# Lock_in.net
KiCad netlist of a schematic drawn in EAGLE
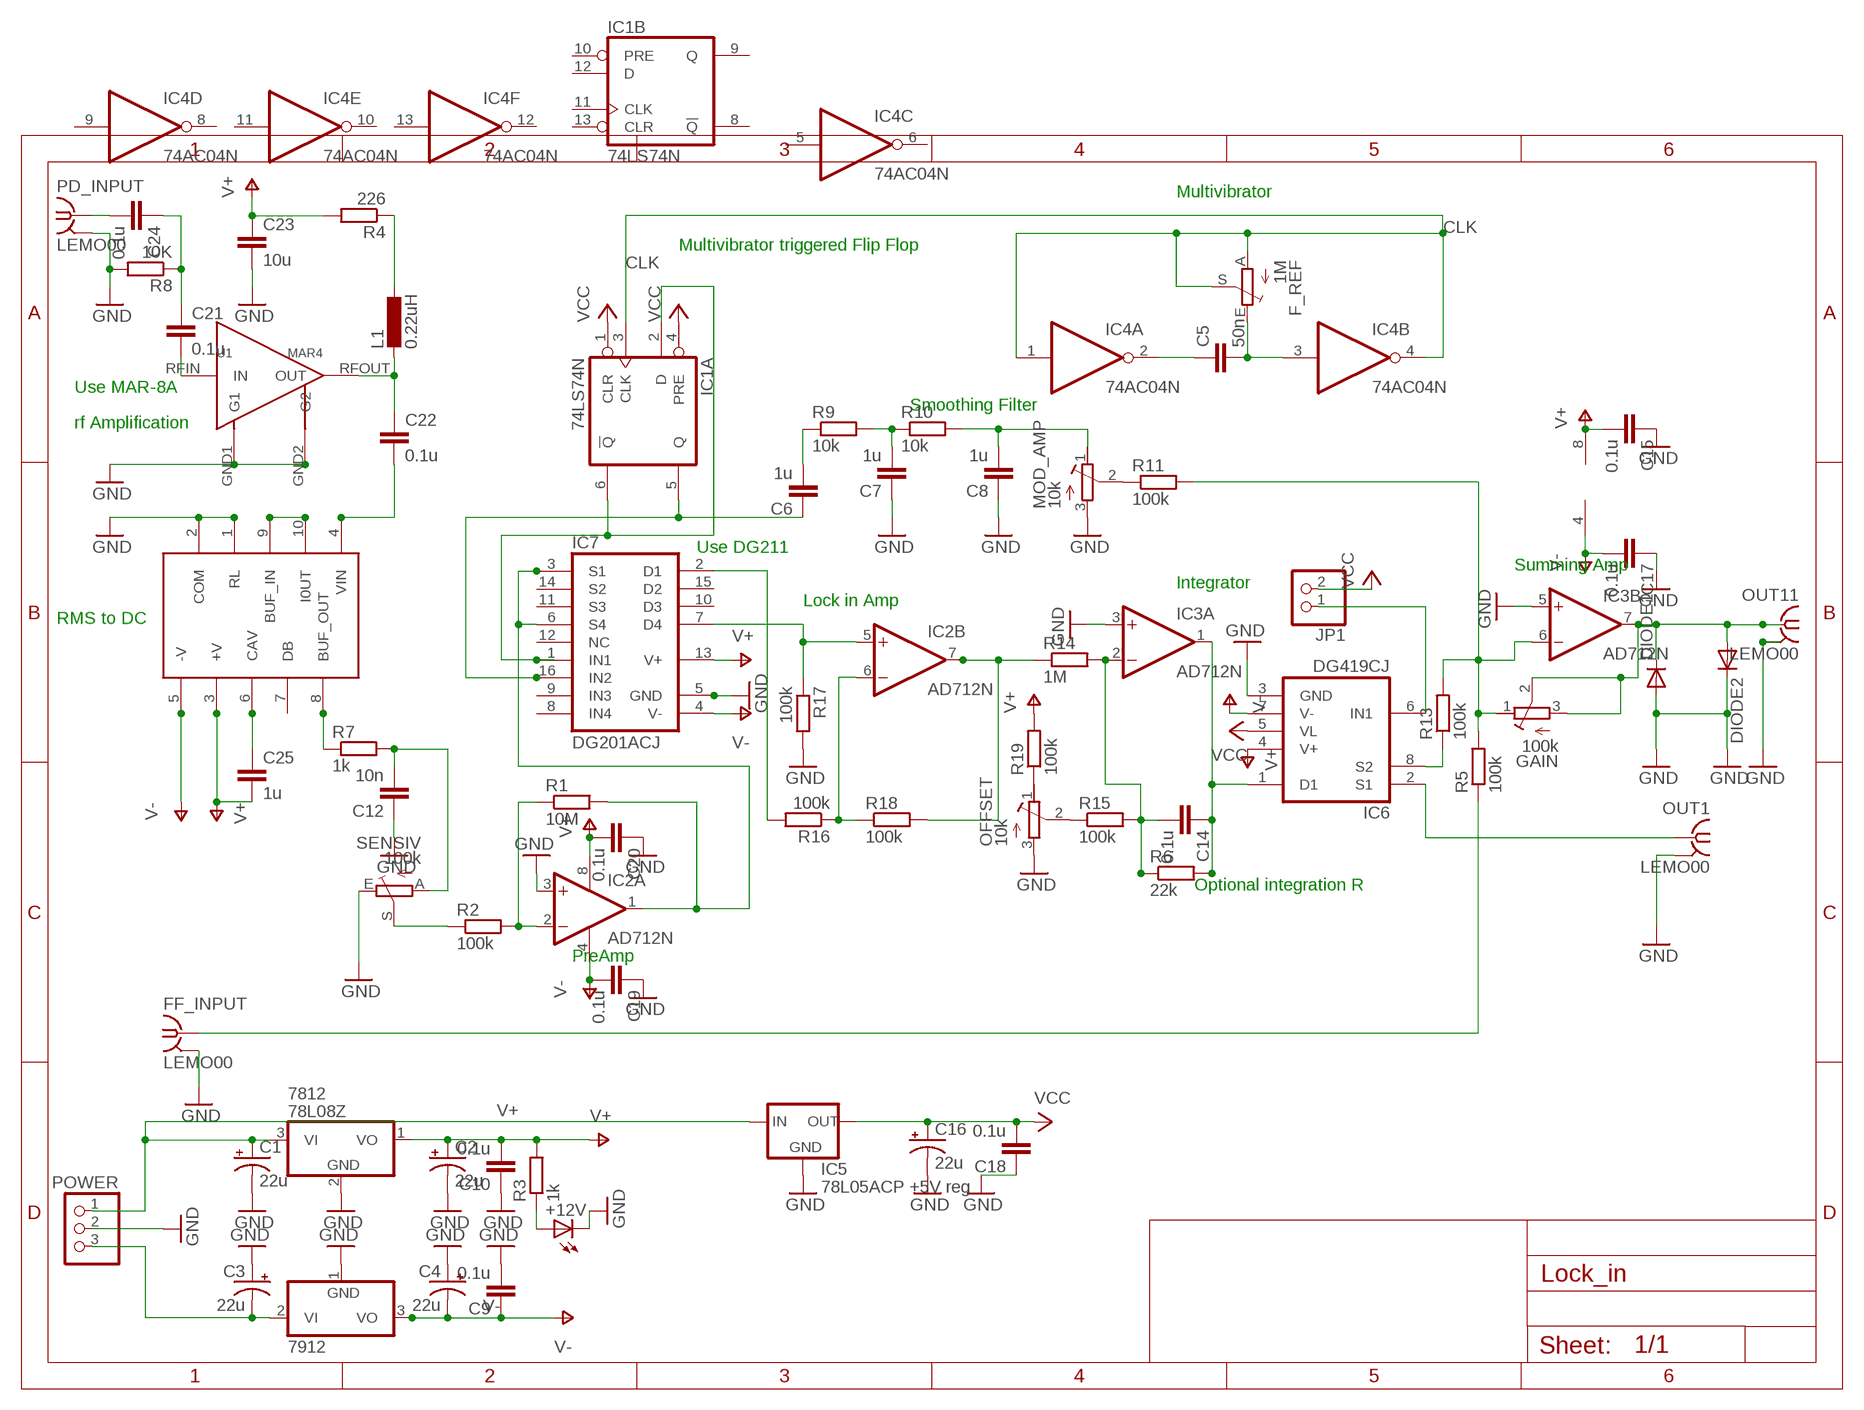
[diagram p0: schematic, sheet 1]

(export (version "E")
  (design (tool "Eeschema 10.0.6"))
  (components
    (comp (ref "+12V")
      (value "LED5MM")
      (footprint "eagle-import:LED5MM")
      (libsource (lib "eagle-import") (part "LED5MM"))
    )
    (comp (ref "7812")
      (value "78L08Z")
      (footprint "eagle-import:TO92")
      (libsource (lib "eagle-import") (part "78ZL08"))
    )
    (comp (ref "7912")
      (value "79L12Z")
      (footprint "eagle-import:TO92")
      (libsource (lib "eagle-import") (part "79ZL12"))
    )
    (comp (ref "C1")
      (value "22u")
      (footprint "eagle-import:E5-4")
      (libsource (lib "eagle-import") (part "CPOL-USE5-4"))
    )
    (comp (ref "C2")
      (value "22u")
      (footprint "eagle-import:E5-4")
      (libsource (lib "eagle-import") (part "CPOL-USE5-4"))
    )
    (comp (ref "C3")
      (value "22u")
      (footprint "eagle-import:E5-4")
      (libsource (lib "eagle-import") (part "CPOL-USE5-4"))
    )
    (comp (ref "C4")
      (value "22u")
      (footprint "eagle-import:E5-4")
      (libsource (lib "eagle-import") (part "CPOL-USE5-4"))
    )
    (comp (ref "C5")
      (value "50n")
      (footprint "eagle-import:C050-024X044")
      (libsource (lib "eagle-import") (part "C-EU050-024X044"))
    )
    (comp (ref "C6")
      (value "1u")
      (footprint "eagle-import:C050-024X044")
      (libsource (lib "eagle-import") (part "C-EU050-024X044"))
    )
    (comp (ref "C7")
      (value "1u")
      (footprint "eagle-import:C050-024X044")
      (libsource (lib "eagle-import") (part "C-EU050-024X044"))
    )
    (comp (ref "C8")
      (value "1u")
      (footprint "eagle-import:C050-024X044")
      (libsource (lib "eagle-import") (part "C-EU050-024X044"))
    )
    (comp (ref "C9")
      (value "0.1u")
      (footprint "eagle-import:C050-024X044")
      (libsource (lib "eagle-import") (part "C-EU050-024X044"))
    )
    (comp (ref "C10")
      (value "0.1u")
      (footprint "eagle-import:C050-024X044")
      (libsource (lib "eagle-import") (part "C-EU050-024X044"))
    )
    (comp (ref "C12")
      (value "10n")
      (footprint "eagle-import:C050-024X044")
      (libsource (lib "eagle-import") (part "C-EU050-024X044"))
    )
    (comp (ref "C14")
      (value "0.1u")
      (footprint "eagle-import:C050-024X044")
      (libsource (lib "eagle-import") (part "C-EU050-024X044"))
    )
    (comp (ref "C15")
      (value "0.1u")
      (footprint "eagle-import:C050-024X044")
      (libsource (lib "eagle-import") (part "C-EU050-024X044"))
    )
    (comp (ref "C16")
      (value "22u")
      (footprint "eagle-import:E5-4")
      (libsource (lib "eagle-import") (part "CPOL-USE5-4"))
    )
    (comp (ref "C17")
      (value "0.1u")
      (footprint "eagle-import:C050-024X044")
      (libsource (lib "eagle-import") (part "C-EU050-024X044"))
    )
    (comp (ref "C18")
      (value "0.1u")
      (footprint "eagle-import:C050-024X044")
      (libsource (lib "eagle-import") (part "C-EU050-024X044"))
    )
    (comp (ref "C19")
      (value "0.1u")
      (footprint "eagle-import:C050-024X044")
      (libsource (lib "eagle-import") (part "C-EU050-024X044"))
    )
    (comp (ref "C20")
      (value "0.1u")
      (footprint "eagle-import:C050-024X044")
      (libsource (lib "eagle-import") (part "C-EU050-024X044"))
    )
    (comp (ref "C21")
      (value "0.1u")
      (footprint "eagle-import:C0805")
      (libsource (lib "eagle-import") (part "C-EUC0805"))
    )
    (comp (ref "C22")
      (value "0.1u")
      (footprint "eagle-import:C0805")
      (libsource (lib "eagle-import") (part "C-EUC0805"))
    )
    (comp (ref "C23")
      (value "10u")
      (footprint "eagle-import:C1206")
      (libsource (lib "eagle-import") (part "C-EUC1206"))
    )
    (comp (ref "C24")
      (value "0.1u")
      (footprint "eagle-import:C0805")
      (libsource (lib "eagle-import") (part "C-EUC0805"))
    )
    (comp (ref "C25")
      (value "1u")
      (footprint "eagle-import:C0805")
      (libsource (lib "eagle-import") (part "C-EUC0805"))
    )
    (comp (ref "DIODE1")
      (value "1N4004")
      (footprint "eagle-import:DO41-10")
      (libsource (lib "eagle-import") (part "1N4004"))
    )
    (comp (ref "DIODE2")
      (value "1N4004")
      (footprint "eagle-import:DO41-10")
      (libsource (lib "eagle-import") (part "1N4004"))
    )
    (comp (ref "FF_INPUT")
      (value "LEMO00")
      (footprint "eagle-import:LEMOPAC.PAC")
      (libsource (lib "eagle-import") (part "LEMO00"))
    )
    (comp (ref "F_REF")
      (value "1M")
      (footprint "eagle-import:S63P")
      (libsource (lib "eagle-import") (part "TRIM_EU-S63P"))
    )
    (comp (ref "GAIN")
      (value "100k")
      (footprint "eagle-import:RTRIM43P")
      (libsource (lib "eagle-import") (part "R-TRIMM43P"))
    )
    (comp (ref "IC1")
      (value "74LS74N")
      (footprint "eagle-import:DIL14")
      (libsource (lib "eagle-import") (part "7474NLS"))
    )
    (comp (ref "IC2")
      (value "AD712N")
      (footprint "eagle-import:DIL08")
      (libsource (lib "eagle-import") (part "AD712N"))
    )
    (comp (ref "IC3")
      (value "AD712N")
      (footprint "eagle-import:DIL08")
      (libsource (lib "eagle-import") (part "AD712N"))
    )
    (comp (ref "IC4")
      (value "74AC04N")
      (footprint "eagle-import:DIL14")
      (libsource (lib "eagle-import") (part "7404NAC"))
    )
    (comp (ref "IC5")
      (value "78L05ACP +5V reg")
      (footprint "eagle-import:78LXX")
      (libsource (lib "eagle-import") (part "78LXX"))
    )
    (comp (ref "IC6")
      (value "DG419CJ")
      (footprint "eagle-import:DIL08")
      (fields (field (name "MF") "MAXIM"))
      (libsource (lib "eagle-import") (part "DG419CJ"))
    )
    (comp (ref "IC7")
      (value "DG201ACJ")
      (footprint "eagle-import:DIL16")
      (libsource (lib "eagle-import") (part "DG201ACJ"))
    )
    (comp (ref "JP1")
      (value "PINHD-1X2")
      (footprint "eagle-import:1X02")
      (libsource (lib "eagle-import") (part "PINHD-1X2"))
    )
    (comp (ref "L1")
      (value "0.22uH")
      (footprint "eagle-import:L3216C")
      (libsource (lib "eagle-import") (part "L-EUL3216C"))
    )
    (comp (ref "MOD_AMP")
      (value "10k")
      (footprint "eagle-import:RTRIM43P")
      (libsource (lib "eagle-import") (part "R-TRIMM43P"))
    )
    (comp (ref "OFFSET")
      (value "10k")
      (footprint "eagle-import:RTRIM43P")
      (libsource (lib "eagle-import") (part "R-TRIMM43P"))
    )
    (comp (ref "OUT1")
      (value "LEMO00")
      (footprint "eagle-import:LEMOPAC.PAC")
      (libsource (lib "eagle-import") (part "LEMO00"))
    )
    (comp (ref "OUT11")
      (value "LEMO00")
      (footprint "eagle-import:LEMOPAC.PAC")
      (libsource (lib "eagle-import") (part "LEMO00"))
    )
    (comp (ref "PD_INPUT")
      (value "LEMO00")
      (footprint "eagle-import:LEMOPAC.PAC")
      (libsource (lib "eagle-import") (part "LEMO00"))
    )
    (comp (ref "POWER")
      (value "PINHD-1X3")
      (footprint "eagle-import:1X03")
      (libsource (lib "eagle-import") (part "PINHD-1X3"))
    )
    (comp (ref "R1")
      (value "10M")
      (footprint "eagle-import:0204_7")
      (libsource (lib "eagle-import") (part "R-EU_0204/7"))
    )
    (comp (ref "R2")
      (value "100k")
      (footprint "eagle-import:0204_7")
      (libsource (lib "eagle-import") (part "R-EU_0204/7"))
    )
    (comp (ref "R3")
      (value "1k")
      (footprint "eagle-import:0204_7")
      (libsource (lib "eagle-import") (part "R-EU_0204/7"))
    )
    (comp (ref "R4")
      (value "226")
      (footprint "eagle-import:R1206")
      (libsource (lib "eagle-import") (part "R-EU_R1206"))
    )
    (comp (ref "R5")
      (value "100k")
      (footprint "eagle-import:0204_7")
      (libsource (lib "eagle-import") (part "R-EU_0204/7"))
    )
    (comp (ref "R6")
      (value "22k")
      (footprint "eagle-import:0204_7")
      (libsource (lib "eagle-import") (part "R-EU_0204/7"))
    )
    (comp (ref "R7")
      (value "1k")
      (footprint "eagle-import:0204_7")
      (libsource (lib "eagle-import") (part "R-EU_0204/7"))
    )
    (comp (ref "R8")
      (value "10K")
      (footprint "eagle-import:R1206")
      (libsource (lib "eagle-import") (part "R-EU_R1206"))
    )
    (comp (ref "R9")
      (value "10k")
      (footprint "eagle-import:0204_7")
      (libsource (lib "eagle-import") (part "R-EU_0204/7"))
    )
    (comp (ref "R10")
      (value "10k")
      (footprint "eagle-import:0204_7")
      (libsource (lib "eagle-import") (part "R-EU_0204/7"))
    )
    (comp (ref "R11")
      (value "100k")
      (footprint "eagle-import:0204_7")
      (libsource (lib "eagle-import") (part "R-EU_0204/7"))
    )
    (comp (ref "R13")
      (value "100k")
      (footprint "eagle-import:0204_7")
      (libsource (lib "eagle-import") (part "R-EU_0204/7"))
    )
    (comp (ref "R14")
      (value "1M")
      (footprint "eagle-import:0204_7")
      (libsource (lib "eagle-import") (part "R-EU_0204/7"))
    )
    (comp (ref "R15")
      (value "100k")
      (footprint "eagle-import:0204_7")
      (libsource (lib "eagle-import") (part "R-EU_0204/7"))
    )
    (comp (ref "R16")
      (value "100k")
      (footprint "eagle-import:0204_7")
      (libsource (lib "eagle-import") (part "R-EU_0204/7"))
    )
    (comp (ref "R17")
      (value "100k")
      (footprint "eagle-import:0204_7")
      (libsource (lib "eagle-import") (part "R-EU_0204/7"))
    )
    (comp (ref "R18")
      (value "100k")
      (footprint "eagle-import:0204_7")
      (libsource (lib "eagle-import") (part "R-EU_0204/7"))
    )
    (comp (ref "R19")
      (value "100k")
      (footprint "eagle-import:0204_7")
      (libsource (lib "eagle-import") (part "R-EU_0204/7"))
    )
    (comp (ref "SENSIV")
      (value "100k")
      (footprint "eagle-import:S63P")
      (libsource (lib "eagle-import") (part "TRIM_EU-S63P"))
    )
    (comp (ref "U$1")
      (value "AD636")
      (footprint "eagle-import:TO100")
      (libsource (lib "eagle-import") (part "AD636"))
    )
    (comp (ref "U1")
      (value "MAR4")
      (footprint "eagle-import:VV105")
      (libsource (lib "eagle-import") (part "MAR4"))
    )
  )
  (nets
    (net (code "1") (name "/CLK") (class "Default")
      (node (ref "F_REF") (pin "A") (pinfunction "A_A") (pintype "passive"))
      (node (ref "F_REF") (pin "S") (pinfunction "S_S") (pintype "passive"))
      (node (ref "IC1") (pin "3") (pinfunction "CLK_3") (pintype "input"))
      (node (ref "IC4") (pin "1") (pinfunction "I_1") (pintype "input"))
      (node (ref "IC4") (pin "4") (pinfunction "O_4") (pintype "output"))
    )
    (net (code "2") (name "GND") (class "Default")
      (node (ref "+12V") (pin "K") (pinfunction "C_K") (pintype "passive"))
      (node (ref "7812") (pin "2") (pinfunction "GND_2") (pintype "passive"))
      (node (ref "7912") (pin "1") (pinfunction "GND_1") (pintype "passive"))
      (node (ref "C1") (pin "-") (pinfunction "-_-") (pintype "passive"))
      (node (ref "C10") (pin "1") (pinfunction "1_1") (pintype "passive"))
      (node (ref "C12") (pin "1") (pinfunction "1_1") (pintype "passive"))
      (node (ref "C15") (pin "1") (pinfunction "1_1") (pintype "passive"))
      (node (ref "C16") (pin "-") (pinfunction "-_-") (pintype "passive"))
      (node (ref "C17") (pin "1") (pinfunction "1_1") (pintype "passive"))
      (node (ref "C18") (pin "1") (pinfunction "1_1") (pintype "passive"))
      (node (ref "C19") (pin "1") (pinfunction "1_1") (pintype "passive"))
      (node (ref "C2") (pin "-") (pinfunction "-_-") (pintype "passive"))
      (node (ref "C20") (pin "1") (pinfunction "1_1") (pintype "passive"))
      (node (ref "C23") (pin "2") (pinfunction "2_2") (pintype "passive"))
      (node (ref "C3") (pin "+") (pinfunction "+_+") (pintype "passive"))
      (node (ref "C4") (pin "+") (pinfunction "+_+") (pintype "passive"))
      (node (ref "C7") (pin "1") (pinfunction "1_1") (pintype "passive"))
      (node (ref "C8") (pin "1") (pinfunction "1_1") (pintype "passive"))
      (node (ref "C9") (pin "2") (pinfunction "2_2") (pintype "passive"))
      (node (ref "DIODE1") (pin "A") (pinfunction "A_A") (pintype "passive"))
      (node (ref "DIODE2") (pin "C") (pinfunction "C_C") (pintype "passive"))
      (node (ref "FF_INPUT") (pin "2") (pinfunction "GND_2") (pintype "power_in"))
      (node (ref "FF_INPUT") (pin "3") (pinfunction "GND_3") (pintype "power_in"))
      (node (ref "FF_INPUT") (pin "4") (pinfunction "GND_4") (pintype "power_in"))
      (node (ref "FF_INPUT") (pin "5") (pinfunction "GND_5") (pintype "power_in"))
      (node (ref "IC2") (pin "3") (pinfunction "+IN_3") (pintype "input"))
      (node (ref "IC3") (pin "3") (pinfunction "+IN_3") (pintype "input"))
      (node (ref "IC3") (pin "5") (pinfunction "+IN_5") (pintype "input"))
      (node (ref "IC5") (pin "GND") (pinfunction "GND_GND") (pintype "input"))
      (node (ref "IC6") (pin "3") (pinfunction "GND_3") (pintype "power_in"))
      (node (ref "IC7") (pin "5") (pinfunction "GND_5") (pintype "power_in"))
      (node (ref "MOD_AMP") (pin "3") (pinfunction "E_3") (pintype "passive"))
      (node (ref "OFFSET") (pin "3") (pinfunction "E_3") (pintype "passive"))
      (node (ref "OUT1") (pin "2") (pinfunction "GND_2") (pintype "power_in"))
      (node (ref "OUT1") (pin "3") (pinfunction "GND_3") (pintype "power_in"))
      (node (ref "OUT1") (pin "4") (pinfunction "GND_4") (pintype "power_in"))
      (node (ref "OUT1") (pin "5") (pinfunction "GND_5") (pintype "power_in"))
      (node (ref "OUT11") (pin "2") (pinfunction "GND_2") (pintype "power_in"))
      (node (ref "OUT11") (pin "3") (pinfunction "GND_3") (pintype "power_in"))
      (node (ref "OUT11") (pin "4") (pinfunction "GND_4") (pintype "power_in"))
      (node (ref "OUT11") (pin "5") (pinfunction "GND_5") (pintype "power_in"))
      (node (ref "PD_INPUT") (pin "2") (pinfunction "GND_2") (pintype "power_in"))
      (node (ref "PD_INPUT") (pin "3") (pinfunction "GND_3") (pintype "power_in"))
      (node (ref "PD_INPUT") (pin "4") (pinfunction "GND_4") (pintype "power_in"))
      (node (ref "PD_INPUT") (pin "5") (pinfunction "GND_5") (pintype "power_in"))
      (node (ref "POWER") (pin "2") (pinfunction "2_2") (pintype "passive"))
      (node (ref "R17") (pin "2") (pinfunction "2_2") (pintype "passive"))
      (node (ref "R8") (pin "2") (pinfunction "2_2") (pintype "passive"))
      (node (ref "SENSIV") (pin "E") (pinfunction "E_E") (pintype "passive"))
      (node (ref "U$1") (pin "1") (pinfunction "RL_1") (pintype "output"))
      (node (ref "U$1") (pin "2") (pinfunction "COM_2") (pintype "power_in"))
      (node (ref "U1") (pin "GND1") (pinfunction "G1_GND1") (pintype "power_in"))
      (node (ref "U1") (pin "GND2") (pinfunction "G2_GND2") (pintype "power_in"))
    )
    (net (code "3") (name "Net-(+12V-PadA)") (class "Default")
      (node (ref "+12V") (pin "A") (pinfunction "A_A") (pintype "passive"))
      (node (ref "R3") (pin "1") (pinfunction "1_1") (pintype "passive"))
    )
    (net (code "4") (name "Net-(7812-VI)") (class "Default")
      (node (ref "7812") (pin "3") (pinfunction "VI_3") (pintype "input"))
      (node (ref "C1") (pin "+") (pinfunction "+_+") (pintype "passive"))
      (node (ref "IC5") (pin "IN") (pinfunction "IN_IN") (pintype "input"))
      (node (ref "POWER") (pin "1") (pinfunction "1_1") (pintype "passive"))
    )
    (net (code "5") (name "Net-(7912-VI)") (class "Default")
      (node (ref "7912") (pin "2") (pinfunction "VI_2") (pintype "input"))
      (node (ref "C3") (pin "-") (pinfunction "-_-") (pintype "passive"))
      (node (ref "POWER") (pin "3") (pinfunction "3_3") (pintype "passive"))
    )
    (net (code "6") (name "Net-(C6-Pad2)") (class "Default")
      (node (ref "C6") (pin "2") (pinfunction "2_2") (pintype "passive"))
      (node (ref "R9") (pin "1") (pinfunction "1_1") (pintype "passive"))
    )
    (net (code "7") (name "Net-(C7-Pad2)") (class "Default")
      (node (ref "C7") (pin "2") (pinfunction "2_2") (pintype "passive"))
      (node (ref "R10") (pin "1") (pinfunction "1_1") (pintype "passive"))
      (node (ref "R9") (pin "2") (pinfunction "2_2") (pintype "passive"))
    )
    (net (code "8") (name "Net-(C12-Pad2)") (class "Default")
      (node (ref "C12") (pin "2") (pinfunction "2_2") (pintype "passive"))
      (node (ref "R7") (pin "2") (pinfunction "2_2") (pintype "passive"))
      (node (ref "SENSIV") (pin "A") (pinfunction "A_A") (pintype "passive"))
    )
    (net (code "9") (name "Net-(C21-Pad1)") (class "Default")
      (node (ref "C21") (pin "1") (pinfunction "1_1") (pintype "passive"))
      (node (ref "C24") (pin "1") (pinfunction "1_1") (pintype "passive"))
      (node (ref "R8") (pin "1") (pinfunction "1_1") (pintype "passive"))
    )
    (net (code "10") (name "Net-(C24-Pad2)") (class "Default")
      (node (ref "C24") (pin "2") (pinfunction "2_2") (pintype "passive"))
      (node (ref "PD_INPUT") (pin "1") (pinfunction "1_1") (pintype "passive"))
    )
    (net (code "11") (name "Net-(FF_INPUT-Pad1)") (class "Default")
      (node (ref "FF_INPUT") (pin "1") (pinfunction "1_1") (pintype "passive"))
      (node (ref "R5") (pin "1") (pinfunction "1_1") (pintype "passive"))
    )
    (net (code "12") (name "Net-(GAIN-A)") (class "Default")
      (node (ref "GAIN") (pin "1") (pinfunction "A_1") (pintype "passive"))
      (node (ref "IC3") (pin "6") (pinfunction "-IN_6") (pintype "input"))
      (node (ref "R11") (pin "2") (pinfunction "2_2") (pintype "passive"))
      (node (ref "R13") (pin "2") (pinfunction "2_2") (pintype "passive"))
      (node (ref "R5") (pin "2") (pinfunction "2_2") (pintype "passive"))
    )
    (net (code "13") (name "Net-(GAIN-E)") (class "Default")
      (node (ref "DIODE1") (pin "C") (pinfunction "C_C") (pintype "passive"))
      (node (ref "DIODE2") (pin "A") (pinfunction "A_A") (pintype "passive"))
      (node (ref "GAIN") (pin "2") (pinfunction "S_2") (pintype "passive"))
      (node (ref "GAIN") (pin "3") (pinfunction "E_3") (pintype "passive"))
      (node (ref "IC3") (pin "7") (pinfunction "OUT_7") (pintype "output"))
      (node (ref "OUT11") (pin "1") (pinfunction "1_1") (pintype "passive"))
    )
    (net (code "14") (name "Net-(IC1A-D)") (class "Default")
      (node (ref "IC1") (pin "2") (pinfunction "D_2") (pintype "input"))
      (node (ref "IC1") (pin "6") (pinfunction "~{Q}_6") (pintype "output"))
      (node (ref "IC7") (pin "1") (pinfunction "IN1_1") (pintype "input"))
    )
    (net (code "15") (name "Net-(IC1A-Q)") (class "Default")
      (node (ref "C6") (pin "1") (pinfunction "1_1") (pintype "passive"))
      (node (ref "IC1") (pin "5") (pinfunction "Q_5") (pintype "output"))
      (node (ref "IC7") (pin "16") (pinfunction "IN2_16") (pintype "input"))
    )
    (net (code "16") (name "Net-(IC2A--IN)") (class "Default")
      (node (ref "IC2") (pin "2") (pinfunction "-IN_2") (pintype "input"))
      (node (ref "R1") (pin "1") (pinfunction "1_1") (pintype "passive"))
      (node (ref "R2") (pin "2") (pinfunction "2_2") (pintype "passive"))
    )
    (net (code "17") (name "Net-(IC2A-OUT)") (class "Default")
      (node (ref "IC2") (pin "1") (pinfunction "OUT_1") (pintype "output"))
      (node (ref "IC7") (pin "3") (pinfunction "S1_3") (pintype "passive"))
      (node (ref "IC7") (pin "6") (pinfunction "S4_6") (pintype "passive"))
      (node (ref "R1") (pin "2") (pinfunction "2_2") (pintype "passive"))
    )
    (net (code "18") (name "Net-(IC2B-+IN)") (class "Default")
      (node (ref "IC2") (pin "5") (pinfunction "+IN_5") (pintype "input"))
      (node (ref "IC7") (pin "7") (pinfunction "D4_7") (pintype "passive"))
      (node (ref "R17") (pin "1") (pinfunction "1_1") (pintype "passive"))
    )
    (net (code "19") (name "Net-(IC2B--IN)") (class "Default")
      (node (ref "IC2") (pin "6") (pinfunction "-IN_6") (pintype "input"))
      (node (ref "R16") (pin "1") (pinfunction "1_1") (pintype "passive"))
      (node (ref "R18") (pin "1") (pinfunction "1_1") (pintype "passive"))
    )
    (net (code "20") (name "Net-(IC2B-OUT)") (class "Default")
      (node (ref "IC2") (pin "7") (pinfunction "OUT_7") (pintype "output"))
      (node (ref "R14") (pin "1") (pinfunction "1_1") (pintype "passive"))
      (node (ref "R18") (pin "2") (pinfunction "2_2") (pintype "passive"))
    )
    (net (code "21") (name "Net-(IC3A--IN)") (class "Default")
      (node (ref "C14") (pin "2") (pinfunction "2_2") (pintype "passive"))
      (node (ref "IC3") (pin "2") (pinfunction "-IN_2") (pintype "input"))
      (node (ref "R14") (pin "2") (pinfunction "2_2") (pintype "passive"))
      (node (ref "R15") (pin "2") (pinfunction "2_2") (pintype "passive"))
      (node (ref "R6") (pin "1") (pinfunction "1_1") (pintype "passive"))
    )
    (net (code "22") (name "Net-(IC3A-OUT)") (class "Default")
      (node (ref "C14") (pin "1") (pinfunction "1_1") (pintype "passive"))
      (node (ref "IC3") (pin "1") (pinfunction "OUT_1") (pintype "output"))
      (node (ref "IC6") (pin "1") (pinfunction "D1_1") (pintype "passive"))
      (node (ref "R6") (pin "2") (pinfunction "2_2") (pintype "passive"))
    )
    (net (code "23") (name "Net-(IC4A-O)") (class "Default")
      (node (ref "C5") (pin "1") (pinfunction "1_1") (pintype "passive"))
      (node (ref "IC4") (pin "2") (pinfunction "O_2") (pintype "output"))
    )
    (net (code "24") (name "Net-(IC4B-I)") (class "Default")
      (node (ref "C5") (pin "2") (pinfunction "2_2") (pintype "passive"))
      (node (ref "F_REF") (pin "E") (pinfunction "E_E") (pintype "passive"))
      (node (ref "IC4") (pin "3") (pinfunction "I_3") (pintype "input"))
    )
    (net (code "25") (name "Net-(IC6-IN1)") (class "Default")
      (node (ref "IC6") (pin "6") (pinfunction "IN1_6") (pintype "input"))
      (node (ref "JP1") (pin "1") (pinfunction "1_1") (pintype "passive"))
    )
    (net (code "26") (name "Net-(IC6-S1)") (class "Default")
      (node (ref "IC6") (pin "2") (pinfunction "S1_2") (pintype "passive"))
      (node (ref "OUT1") (pin "1") (pinfunction "1_1") (pintype "passive"))
    )
    (net (code "27") (name "Net-(IC6-S2)") (class "Default")
      (node (ref "IC6") (pin "8") (pinfunction "S2_8") (pintype "passive"))
      (node (ref "R13") (pin "1") (pinfunction "1_1") (pintype "passive"))
    )
    (net (code "28") (name "Net-(IC7-D1)") (class "Default")
      (node (ref "IC7") (pin "2") (pinfunction "D1_2") (pintype "passive"))
      (node (ref "R16") (pin "2") (pinfunction "2_2") (pintype "passive"))
    )
    (net (code "29") (name "Net-(L1-Pad1)") (class "Default")
      (node (ref "L1") (pin "1") (pinfunction "1_1") (pintype "passive"))
      (node (ref "R4") (pin "1") (pinfunction "1_1") (pintype "passive"))
    )
    (net (code "30") (name "Net-(MOD_AMP-A)") (class "Default")
      (node (ref "C8") (pin "2") (pinfunction "2_2") (pintype "passive"))
      (node (ref "MOD_AMP") (pin "1") (pinfunction "A_1") (pintype "passive"))
      (node (ref "R10") (pin "2") (pinfunction "2_2") (pintype "passive"))
    )
    (net (code "31") (name "Net-(MOD_AMP-S)") (class "Default")
      (node (ref "MOD_AMP") (pin "2") (pinfunction "S_2") (pintype "passive"))
      (node (ref "R11") (pin "1") (pinfunction "1_1") (pintype "passive"))
    )
    (net (code "32") (name "Net-(OFFSET-A)") (class "Default")
      (node (ref "OFFSET") (pin "1") (pinfunction "A_1") (pintype "passive"))
      (node (ref "R19") (pin "1") (pinfunction "1_1") (pintype "passive"))
    )
    (net (code "33") (name "Net-(OFFSET-S)") (class "Default")
      (node (ref "OFFSET") (pin "2") (pinfunction "S_2") (pintype "passive"))
      (node (ref "R15") (pin "1") (pinfunction "1_1") (pintype "passive"))
    )
    (net (code "34") (name "Net-(R2-Pad1)") (class "Default")
      (node (ref "R2") (pin "1") (pinfunction "1_1") (pintype "passive"))
      (node (ref "SENSIV") (pin "S") (pinfunction "S_S") (pintype "passive"))
    )
    (net (code "35") (name "Net-(U$1-BUF_IN)") (class "Default")
      (node (ref "U$1") (pin "10") (pinfunction "I0UT_10") (pintype "output"))
      (node (ref "U$1") (pin "9") (pinfunction "BUF_IN_9") (pintype "bidirectional"))
    )
    (net (code "36") (name "Net-(U$1-BUF_OUT)") (class "Default")
      (node (ref "R7") (pin "1") (pinfunction "1_1") (pintype "passive"))
      (node (ref "U$1") (pin "8") (pinfunction "BUF_OUT_8") (pintype "output"))
    )
    (net (code "37") (name "Net-(U$1-CAV)") (class "Default")
      (node (ref "C25") (pin "1") (pinfunction "1_1") (pintype "passive"))
      (node (ref "U$1") (pin "6") (pinfunction "CAV_6") (pintype "input"))
    )
    (net (code "38") (name "Net-(U$1-VIN)") (class "Default")
      (node (ref "C22") (pin "2") (pinfunction "2_2") (pintype "passive"))
      (node (ref "U$1") (pin "4") (pinfunction "VIN_4") (pintype "input"))
    )
    (net (code "39") (name "Net-(U1-IN)") (class "Default")
      (node (ref "C21") (pin "2") (pinfunction "2_2") (pintype "passive"))
      (node (ref "U1") (pin "RFIN") (pinfunction "IN_RFIN") (pintype "input"))
    )
    (net (code "40") (name "Net-(U1-OUT)") (class "Default")
      (node (ref "C22") (pin "1") (pinfunction "1_1") (pintype "passive"))
      (node (ref "L1") (pin "2") (pinfunction "2_2") (pintype "passive"))
      (node (ref "U1") (pin "RFOUT") (pinfunction "OUT_RFOUT") (pintype "output"))
    )
    (net (code "41") (name "V+") (class "Default")
      (node (ref "7812") (pin "1") (pinfunction "VO_1") (pintype "passive"))
      (node (ref "C10") (pin "2") (pinfunction "2_2") (pintype "passive"))
      (node (ref "C15") (pin "2") (pinfunction "2_2") (pintype "passive"))
      (node (ref "C2") (pin "+") (pinfunction "+_+") (pintype "passive"))
      (node (ref "C20") (pin "2") (pinfunction "2_2") (pintype "passive"))
      (node (ref "C23") (pin "1") (pinfunction "1_1") (pintype "passive"))
      (node (ref "C25") (pin "2") (pinfunction "2_2") (pintype "passive"))
      (node (ref "IC2") (pin "8") (pinfunction "V+_8") (pintype "power_in"))
      (node (ref "IC3") (pin "8") (pinfunction "V+_8") (pintype "power_in"))
      (node (ref "IC6") (pin "4") (pinfunction "V+_4") (pintype "power_in"))
      (node (ref "IC7") (pin "13") (pinfunction "V+_13") (pintype "power_in"))
      (node (ref "R19") (pin "2") (pinfunction "2_2") (pintype "passive"))
      (node (ref "R3") (pin "2") (pinfunction "2_2") (pintype "passive"))
      (node (ref "R4") (pin "2") (pinfunction "2_2") (pintype "passive"))
      (node (ref "U$1") (pin "3") (pinfunction "+V_3") (pintype "power_in"))
    )
    (net (code "42") (name "V-") (class "Default")
      (node (ref "7912") (pin "3") (pinfunction "VO_3") (pintype "passive"))
      (node (ref "C17") (pin "2") (pinfunction "2_2") (pintype "passive"))
      (node (ref "C19") (pin "2") (pinfunction "2_2") (pintype "passive"))
      (node (ref "C4") (pin "-") (pinfunction "-_-") (pintype "passive"))
      (node (ref "C9") (pin "1") (pinfunction "1_1") (pintype "passive"))
      (node (ref "IC2") (pin "4") (pinfunction "V-_4") (pintype "power_in"))
      (node (ref "IC3") (pin "4") (pinfunction "V-_4") (pintype "power_in"))
      (node (ref "IC6") (pin "7") (pinfunction "V-_7") (pintype "power_in"))
      (node (ref "IC7") (pin "4") (pinfunction "V-_4") (pintype "power_in"))
      (node (ref "U$1") (pin "5") (pinfunction "-V_5") (pintype "power_in"))
    )
    (net (code "43") (name "VCC") (class "Default")
      (node (ref "C16") (pin "+") (pinfunction "+_+") (pintype "passive"))
      (node (ref "C18") (pin "2") (pinfunction "2_2") (pintype "passive"))
      (node (ref "IC1") (pin "1") (pinfunction "CLR_1") (pintype "input"))
      (node (ref "IC1") (pin "4") (pinfunction "PRE_4") (pintype "input"))
      (node (ref "IC5") (pin "OUT") (pinfunction "OUT_OUT") (pintype "passive"))
      (node (ref "IC6") (pin "5") (pinfunction "VL_5") (pintype "power_in"))
      (node (ref "JP1") (pin "2") (pinfunction "2_2") (pintype "passive"))
    )
    (net (code "44") (name "unconnected-(IC1B-CLK-Pad11)") (class "Default")
      (node (ref "IC1") (pin "11") (pinfunction "CLK_11") (pintype "input"))
    )
    (net (code "45") (name "unconnected-(IC1B-CLR-Pad13)") (class "Default")
      (node (ref "IC1") (pin "13") (pinfunction "CLR_13") (pintype "input"))
    )
    (net (code "46") (name "unconnected-(IC1B-D-Pad12)") (class "Default")
      (node (ref "IC1") (pin "12") (pinfunction "D_12") (pintype "input"))
    )
    (net (code "47") (name "unconnected-(IC1B-PRE-Pad10)") (class "Default")
      (node (ref "IC1") (pin "10") (pinfunction "PRE_10") (pintype "input"))
    )
    (net (code "48") (name "unconnected-(IC1B-Q-Pad9)") (class "Default")
      (node (ref "IC1") (pin "9") (pinfunction "Q_9") (pintype "output"))
    )
    (net (code "49") (name "unconnected-(IC1B-~{Q}-Pad8)") (class "Default")
      (node (ref "IC1") (pin "8") (pinfunction "~{Q}_8") (pintype "output"))
    )
    (net (code "50") (name "unconnected-(IC4C-I-Pad5)") (class "Default")
      (node (ref "IC4") (pin "5") (pinfunction "I_5") (pintype "input"))
    )
    (net (code "51") (name "unconnected-(IC4C-O-Pad6)") (class "Default")
      (node (ref "IC4") (pin "6") (pinfunction "O_6") (pintype "output"))
    )
    (net (code "52") (name "unconnected-(IC4D-I-Pad9)") (class "Default")
      (node (ref "IC4") (pin "9") (pinfunction "I_9") (pintype "input"))
    )
    (net (code "53") (name "unconnected-(IC4D-O-Pad8)") (class "Default")
      (node (ref "IC4") (pin "8") (pinfunction "O_8") (pintype "output"))
    )
    (net (code "54") (name "unconnected-(IC4E-I-Pad11)") (class "Default")
      (node (ref "IC4") (pin "11") (pinfunction "I_11") (pintype "input"))
    )
    (net (code "55") (name "unconnected-(IC4E-O-Pad10)") (class "Default")
      (node (ref "IC4") (pin "10") (pinfunction "O_10") (pintype "output"))
    )
    (net (code "56") (name "unconnected-(IC4F-I-Pad13)") (class "Default")
      (node (ref "IC4") (pin "13") (pinfunction "I_13") (pintype "input"))
    )
    (net (code "57") (name "unconnected-(IC4F-O-Pad12)") (class "Default")
      (node (ref "IC4") (pin "12") (pinfunction "O_12") (pintype "output"))
    )
    (net (code "58") (name "unconnected-(IC7-D2-Pad15)") (class "Default")
      (node (ref "IC7") (pin "15") (pinfunction "D2_15") (pintype "passive"))
    )
    (net (code "59") (name "unconnected-(IC7-D3-Pad10)") (class "Default")
      (node (ref "IC7") (pin "10") (pinfunction "D3_10") (pintype "passive"))
    )
    (net (code "60") (name "unconnected-(IC7-IN3-Pad9)") (class "Default")
      (node (ref "IC7") (pin "9") (pinfunction "IN3_9") (pintype "input"))
    )
    (net (code "61") (name "unconnected-(IC7-IN4-Pad8)") (class "Default")
      (node (ref "IC7") (pin "8") (pinfunction "IN4_8") (pintype "input"))
    )
    (net (code "62") (name "unconnected-(IC7-NC-Pad12)") (class "Default")
      (node (ref "IC7") (pin "12") (pinfunction "NC_12") (pintype "no_connect"))
    )
    (net (code "63") (name "unconnected-(IC7-S2-Pad14)") (class "Default")
      (node (ref "IC7") (pin "14") (pinfunction "S2_14") (pintype "passive"))
    )
    (net (code "64") (name "unconnected-(IC7-S3-Pad11)") (class "Default")
      (node (ref "IC7") (pin "11") (pinfunction "S3_11") (pintype "passive"))
    )
    (net (code "65") (name "unconnected-(U$1-DB-Pad7)") (class "Default")
      (node (ref "U$1") (pin "7") (pinfunction "DB_7") (pintype "output"))
    )
  )
)
